# Music_Player_Module.net
KiCad netlist of a schematic drawn in EasyEDA
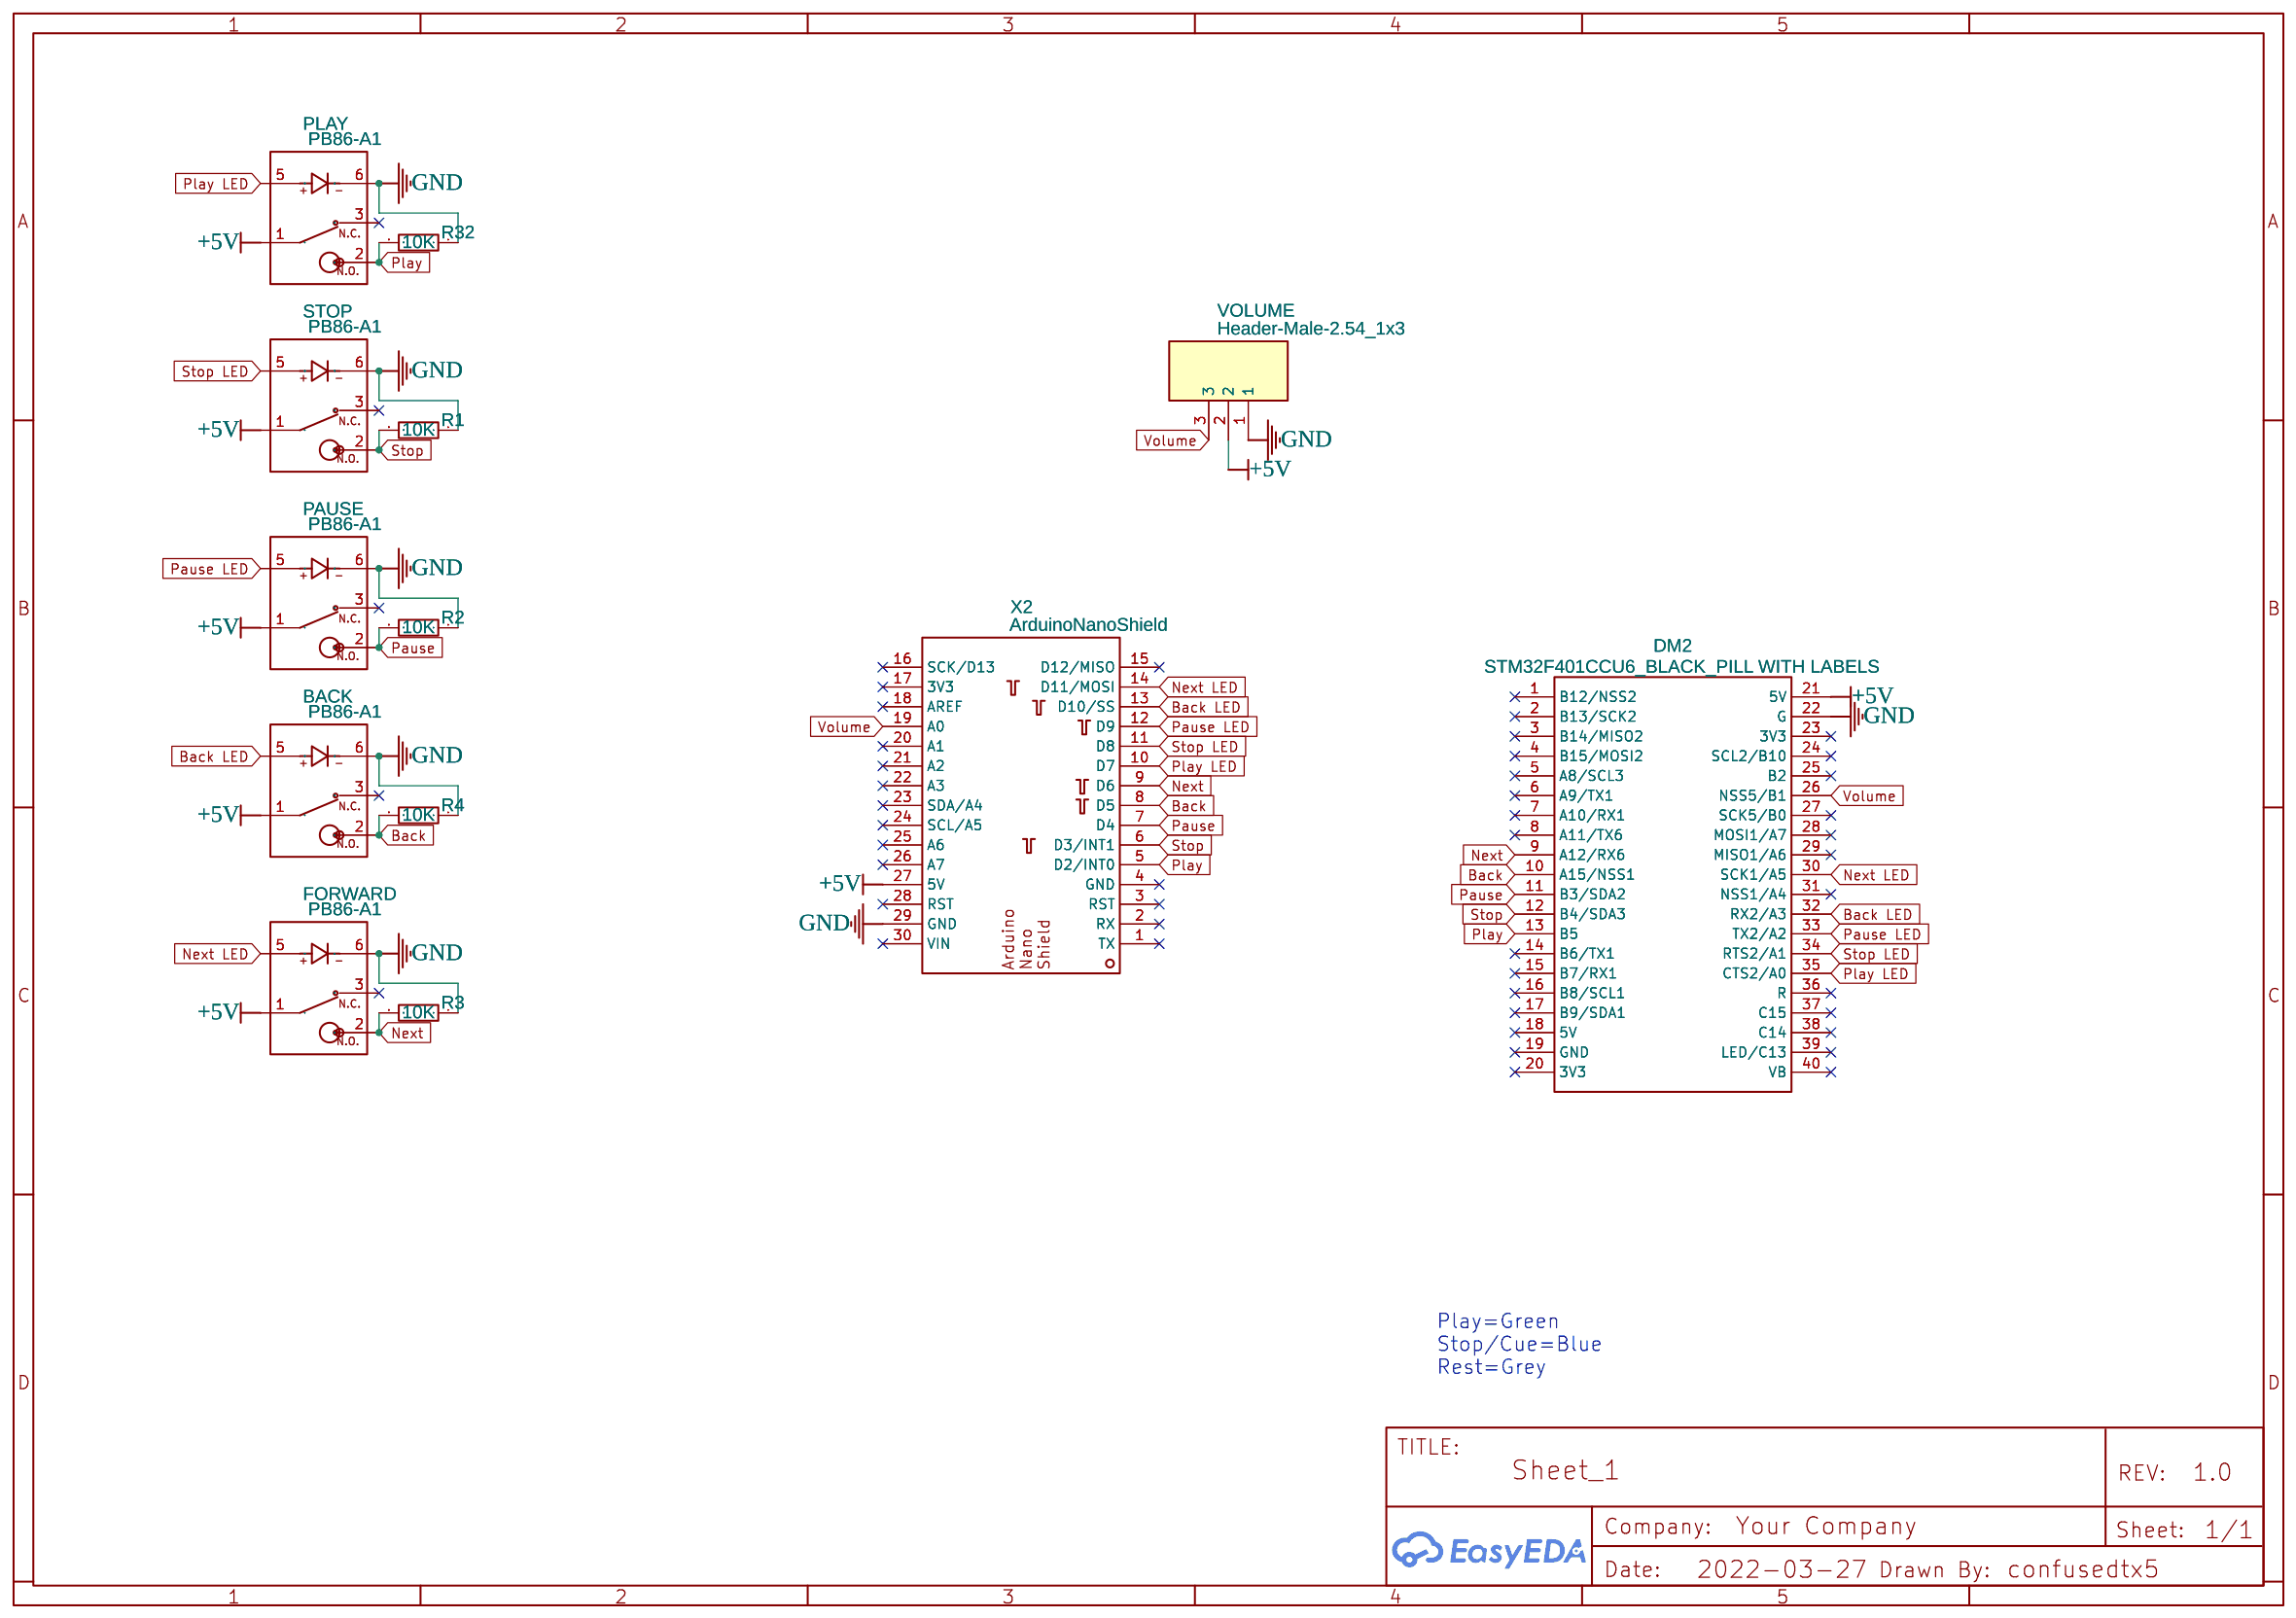
[diagram p0: schematic sheet]

(export (version "E")
  (design (tool "Eeschema 10.0.6"))
  (components
    (comp (ref "BACK") (value "PB86-A1") (libsource (lib "") (part "PB86-A1_3")))
    (comp (ref "DM2")
      (value "STM32F401CCU6_BLACK_PILL WITH LABELS")
      (libsource (lib "") (part "STM32F401CCU6_BLACK_PILL WITH LABELS"))
    )
    (comp (ref "FORWARD") (value "PB86-A1") (libsource (lib "") (part "PB86-A1")))
    (comp (ref "PAUSE") (value "PB86-A1") (libsource (lib "") (part "PB86-A1_4")))
    (comp (ref "PLAY") (value "PB86-A1") (libsource (lib "") (part "PB86-A1_1")))
    (comp (ref "R1")
      (value "10K")
      (fields
        (field (name "BOM_Manufacturer Part") "ESR03EZPJ103")
        (field (name "BOM_Supplier Part") "C253330")
      )
      (libsource (lib "") (part "ESR03EZPJ103"))
    )
    (comp (ref "R2")
      (value "10K")
      (fields
        (field (name "BOM_Manufacturer Part") "ESR03EZPJ103")
        (field (name "BOM_Supplier Part") "C253330")
      )
      (libsource (lib "") (part "ESR03EZPJ103"))
    )
    (comp (ref "R3")
      (value "10K")
      (fields
        (field (name "BOM_Manufacturer Part") "ESR03EZPJ103")
        (field (name "BOM_Supplier Part") "C253330")
      )
      (libsource (lib "") (part "ESR03EZPJ103"))
    )
    (comp (ref "R4")
      (value "10K")
      (fields
        (field (name "BOM_Manufacturer Part") "ESR03EZPJ103")
        (field (name "BOM_Supplier Part") "C253330")
      )
      (libsource (lib "") (part "ESR03EZPJ103"))
    )
    (comp (ref "R32")
      (value "10K")
      (fields
        (field (name "BOM_Manufacturer Part") "ESR03EZPJ103")
        (field (name "BOM_Supplier Part") "C253330")
      )
      (libsource (lib "") (part "ESR03EZPJ103"))
    )
    (comp (ref "STOP") (value "PB86-A1") (libsource (lib "") (part "PB86-A1_2")))
    (comp (ref "VOLUME")
      (value "Header-Male-2.54_1x3")
      (fields (field (name "BOM_Manufacturer Part") "Header-Male-2.54_1x10"))
      (libsource (lib "") (part "Header-Male-2.54_1x3"))
    )
    (comp (ref "X2") (value "ArduinoNanoShield") (libsource (lib "") (part "ArduinoNanoShield")))
  )
  (nets
    (net (code "1") (name "+5V") (class "Default")
      (node (ref "BACK") (pin "1") (pinfunction "1_1") (pintype "unspecified"))
      (node (ref "DM2") (pin "21") (pinfunction "5V_21") (pintype "unspecified"))
      (node (ref "FORWARD") (pin "1") (pinfunction "1_1") (pintype "unspecified"))
      (node (ref "PAUSE") (pin "1") (pinfunction "1_1") (pintype "unspecified"))
      (node (ref "PLAY") (pin "1") (pinfunction "1_1") (pintype "unspecified"))
      (node (ref "STOP") (pin "1") (pinfunction "1_1") (pintype "unspecified"))
      (node (ref "VOLUME") (pin "2") (pinfunction "2_2") (pintype "unspecified"))
      (node (ref "X2") (pin "27") (pinfunction "5V_27") (pintype "unspecified"))
    )
    (net (code "2") (name "Back") (class "Default")
      (node (ref "BACK") (pin "2") (pinfunction "2_2") (pintype "unspecified"))
      (node (ref "DM2") (pin "10") (pinfunction "A15/NSS1_10") (pintype "unspecified"))
      (node (ref "R4") (pin "2") (pinfunction "2_2") (pintype "unspecified"))
      (node (ref "X2") (pin "8") (pinfunction "D5_8") (pintype "unspecified"))
    )
    (net (code "3") (name "Back LED") (class "Default")
      (node (ref "BACK") (pin "5") (pinfunction "5_5") (pintype "unspecified"))
      (node (ref "DM2") (pin "32") (pinfunction "RX2/A3_32") (pintype "unspecified"))
      (node (ref "X2") (pin "13") (pinfunction "D10/SS_13") (pintype "unspecified"))
    )
    (net (code "4") (name "GND") (class "Default")
      (node (ref "BACK") (pin "6") (pinfunction "6_6") (pintype "unspecified"))
      (node (ref "DM2") (pin "22") (pinfunction "G_22") (pintype "unspecified"))
      (node (ref "FORWARD") (pin "6") (pinfunction "6_6") (pintype "unspecified"))
      (node (ref "PAUSE") (pin "6") (pinfunction "6_6") (pintype "unspecified"))
      (node (ref "PLAY") (pin "6") (pinfunction "6_6") (pintype "unspecified"))
      (node (ref "R1") (pin "1") (pinfunction "1_1") (pintype "unspecified"))
      (node (ref "R2") (pin "1") (pinfunction "1_1") (pintype "unspecified"))
      (node (ref "R3") (pin "1") (pinfunction "1_1") (pintype "unspecified"))
      (node (ref "R32") (pin "1") (pinfunction "1_1") (pintype "unspecified"))
      (node (ref "R4") (pin "1") (pinfunction "1_1") (pintype "unspecified"))
      (node (ref "STOP") (pin "6") (pinfunction "6_6") (pintype "unspecified"))
      (node (ref "VOLUME") (pin "1") (pinfunction "1_1") (pintype "unspecified"))
      (node (ref "X2") (pin "29") (pinfunction "GND_29") (pintype "unspecified"))
    )
    (net (code "5") (name "Next") (class "Default")
      (node (ref "DM2") (pin "9") (pinfunction "A12/RX6_9") (pintype "unspecified"))
      (node (ref "FORWARD") (pin "2") (pinfunction "2_2") (pintype "unspecified"))
      (node (ref "R3") (pin "2") (pinfunction "2_2") (pintype "unspecified"))
      (node (ref "X2") (pin "9") (pinfunction "D6_9") (pintype "unspecified"))
    )
    (net (code "6") (name "Next LED") (class "Default")
      (node (ref "DM2") (pin "30") (pinfunction "SCK1/A5_30") (pintype "unspecified"))
      (node (ref "FORWARD") (pin "5") (pinfunction "5_5") (pintype "unspecified"))
      (node (ref "X2") (pin "14") (pinfunction "D11/MOSI_14") (pintype "unspecified"))
    )
    (net (code "7") (name "Pause") (class "Default")
      (node (ref "DM2") (pin "11") (pinfunction "B3/SDA2_11") (pintype "unspecified"))
      (node (ref "PAUSE") (pin "2") (pinfunction "2_2") (pintype "unspecified"))
      (node (ref "R2") (pin "2") (pinfunction "2_2") (pintype "unspecified"))
      (node (ref "X2") (pin "7") (pinfunction "D4_7") (pintype "unspecified"))
    )
    (net (code "8") (name "Pause LED") (class "Default")
      (node (ref "DM2") (pin "33") (pinfunction "TX2/A2_33") (pintype "unspecified"))
      (node (ref "PAUSE") (pin "5") (pinfunction "5_5") (pintype "unspecified"))
      (node (ref "X2") (pin "12") (pinfunction "D9_12") (pintype "unspecified"))
    )
    (net (code "9") (name "Play") (class "Default")
      (node (ref "DM2") (pin "13") (pinfunction "B5_13") (pintype "unspecified"))
      (node (ref "PLAY") (pin "2") (pinfunction "2_2") (pintype "unspecified"))
      (node (ref "R32") (pin "2") (pinfunction "2_2") (pintype "unspecified"))
      (node (ref "X2") (pin "5") (pinfunction "D2/INT0_5") (pintype "unspecified"))
    )
    (net (code "10") (name "Play LED") (class "Default")
      (node (ref "DM2") (pin "35") (pinfunction "CTS2/A0_35") (pintype "unspecified"))
      (node (ref "PLAY") (pin "5") (pinfunction "5_5") (pintype "unspecified"))
      (node (ref "X2") (pin "10") (pinfunction "D7_10") (pintype "unspecified"))
    )
    (net (code "11") (name "Stop") (class "Default")
      (node (ref "DM2") (pin "12") (pinfunction "B4/SDA3_12") (pintype "unspecified"))
      (node (ref "R1") (pin "2") (pinfunction "2_2") (pintype "unspecified"))
      (node (ref "STOP") (pin "2") (pinfunction "2_2") (pintype "unspecified"))
      (node (ref "X2") (pin "6") (pinfunction "D3/INT1_6") (pintype "unspecified"))
    )
    (net (code "12") (name "Stop LED") (class "Default")
      (node (ref "DM2") (pin "34") (pinfunction "RTS2/A1_34") (pintype "unspecified"))
      (node (ref "STOP") (pin "5") (pinfunction "5_5") (pintype "unspecified"))
      (node (ref "X2") (pin "11") (pinfunction "D8_11") (pintype "unspecified"))
    )
    (net (code "13") (name "Volume") (class "Default")
      (node (ref "DM2") (pin "26") (pinfunction "NSS5/B1_26") (pintype "unspecified"))
      (node (ref "VOLUME") (pin "3") (pinfunction "3_3") (pintype "unspecified"))
      (node (ref "X2") (pin "19") (pinfunction "A0_19") (pintype "unspecified"))
    )
    (net (code "14") (name "unconnected-(BACK-Pad3)") (class "Default")
      (node (ref "BACK") (pin "3") (pinfunction "3_3") (pintype "unspecified+no_connect"))
    )
    (net (code "15") (name "unconnected-(DM2-3V3-Pad20)") (class "Default")
      (node (ref "DM2") (pin "20") (pinfunction "3V3_20") (pintype "unspecified+no_connect"))
    )
    (net (code "16") (name "unconnected-(DM2-3V3-Pad23)") (class "Default")
      (node (ref "DM2") (pin "23") (pinfunction "3V3_23") (pintype "unspecified+no_connect"))
    )
    (net (code "17") (name "unconnected-(DM2-5V-Pad18)") (class "Default")
      (node (ref "DM2") (pin "18") (pinfunction "5V_18") (pintype "unspecified+no_connect"))
    )
    (net (code "18") (name "unconnected-(DM2-A8{slash}SCL3-Pad5)") (class "Default")
      (node (ref "DM2") (pin "5") (pinfunction "A8/SCL3_5") (pintype "unspecified+no_connect"))
    )
    (net (code "19") (name "unconnected-(DM2-A9{slash}TX1-Pad6)") (class "Default")
      (node (ref "DM2") (pin "6") (pinfunction "A9/TX1_6") (pintype "unspecified+no_connect"))
    )
    (net (code "20") (name "unconnected-(DM2-A10{slash}RX1-Pad7)") (class "Default")
      (node (ref "DM2") (pin "7") (pinfunction "A10/RX1_7") (pintype "unspecified+no_connect"))
    )
    (net (code "21") (name "unconnected-(DM2-A11{slash}TX6-Pad8)") (class "Default")
      (node (ref "DM2") (pin "8") (pinfunction "A11/TX6_8") (pintype "unspecified+no_connect"))
    )
    (net (code "22") (name "unconnected-(DM2-B2-Pad25)") (class "Default")
      (node (ref "DM2") (pin "25") (pinfunction "B2_25") (pintype "unspecified+no_connect"))
    )
    (net (code "23") (name "unconnected-(DM2-B6{slash}TX1-Pad14)") (class "Default")
      (node (ref "DM2") (pin "14") (pinfunction "B6/TX1_14") (pintype "unspecified+no_connect"))
    )
    (net (code "24") (name "unconnected-(DM2-B7{slash}RX1-Pad15)") (class "Default")
      (node (ref "DM2") (pin "15") (pinfunction "B7/RX1_15") (pintype "unspecified+no_connect"))
    )
    (net (code "25") (name "unconnected-(DM2-B8{slash}SCL1-Pad16)") (class "Default")
      (node (ref "DM2") (pin "16") (pinfunction "B8/SCL1_16") (pintype "unspecified+no_connect"))
    )
    (net (code "26") (name "unconnected-(DM2-B9{slash}SDA1-Pad17)") (class "Default")
      (node (ref "DM2") (pin "17") (pinfunction "B9/SDA1_17") (pintype "unspecified+no_connect"))
    )
    (net (code "27") (name "unconnected-(DM2-B12{slash}NSS2-Pad1)") (class "Default")
      (node (ref "DM2") (pin "1") (pinfunction "B12/NSS2_1") (pintype "unspecified+no_connect"))
    )
    (net (code "28") (name "unconnected-(DM2-B13{slash}SCK2-Pad2)") (class "Default")
      (node (ref "DM2") (pin "2") (pinfunction "B13/SCK2_2") (pintype "unspecified+no_connect"))
    )
    (net (code "29") (name "unconnected-(DM2-B14{slash}MISO2-Pad3)") (class "Default")
      (node (ref "DM2") (pin "3") (pinfunction "B14/MISO2_3") (pintype "unspecified+no_connect"))
    )
    (net (code "30") (name "unconnected-(DM2-B15{slash}MOSI2-Pad4)") (class "Default")
      (node (ref "DM2") (pin "4") (pinfunction "B15/MOSI2_4") (pintype "unspecified+no_connect"))
    )
    (net (code "31") (name "unconnected-(DM2-C14-Pad38)") (class "Default")
      (node (ref "DM2") (pin "38") (pinfunction "C14_38") (pintype "unspecified+no_connect"))
    )
    (net (code "32") (name "unconnected-(DM2-C15-Pad37)") (class "Default")
      (node (ref "DM2") (pin "37") (pinfunction "C15_37") (pintype "unspecified+no_connect"))
    )
    (net (code "33") (name "unconnected-(DM2-GND-Pad19)") (class "Default")
      (node (ref "DM2") (pin "19") (pinfunction "GND_19") (pintype "unspecified+no_connect"))
    )
    (net (code "34") (name "unconnected-(DM2-LED{slash}C13-Pad39)") (class "Default")
      (node (ref "DM2") (pin "39") (pinfunction "LED/C13_39") (pintype "unspecified+no_connect"))
    )
    (net (code "35") (name "unconnected-(DM2-MISO1{slash}A6-Pad29)") (class "Default")
      (node (ref "DM2") (pin "29") (pinfunction "MISO1/A6_29") (pintype "unspecified+no_connect"))
    )
    (net (code "36") (name "unconnected-(DM2-MOSI1{slash}A7-Pad28)") (class "Default")
      (node (ref "DM2") (pin "28") (pinfunction "MOSI1/A7_28") (pintype "unspecified+no_connect"))
    )
    (net (code "37") (name "unconnected-(DM2-NSS1{slash}A4-Pad31)") (class "Default")
      (node (ref "DM2") (pin "31") (pinfunction "NSS1/A4_31") (pintype "unspecified+no_connect"))
    )
    (net (code "38") (name "unconnected-(DM2-R-Pad36)") (class "Default")
      (node (ref "DM2") (pin "36") (pinfunction "R_36") (pintype "unspecified+no_connect"))
    )
    (net (code "39") (name "unconnected-(DM2-SCK5{slash}B0-Pad27)") (class "Default")
      (node (ref "DM2") (pin "27") (pinfunction "SCK5/B0_27") (pintype "unspecified+no_connect"))
    )
    (net (code "40") (name "unconnected-(DM2-SCL2{slash}B10-Pad24)") (class "Default")
      (node (ref "DM2") (pin "24") (pinfunction "SCL2/B10_24") (pintype "unspecified+no_connect"))
    )
    (net (code "41") (name "unconnected-(DM2-VB-Pad40)") (class "Default")
      (node (ref "DM2") (pin "40") (pinfunction "VB_40") (pintype "unspecified+no_connect"))
    )
    (net (code "42") (name "unconnected-(FORWARD-Pad3)") (class "Default")
      (node (ref "FORWARD") (pin "3") (pinfunction "3_3") (pintype "unspecified+no_connect"))
    )
    (net (code "43") (name "unconnected-(PAUSE-Pad3)") (class "Default")
      (node (ref "PAUSE") (pin "3") (pinfunction "3_3") (pintype "unspecified+no_connect"))
    )
    (net (code "44") (name "unconnected-(PLAY-Pad3)") (class "Default")
      (node (ref "PLAY") (pin "3") (pinfunction "3_3") (pintype "unspecified+no_connect"))
    )
    (net (code "45") (name "unconnected-(STOP-Pad3)") (class "Default")
      (node (ref "STOP") (pin "3") (pinfunction "3_3") (pintype "unspecified+no_connect"))
    )
    (net (code "46") (name "unconnected-(X2-3V3-Pad17)") (class "Default")
      (node (ref "X2") (pin "17") (pinfunction "3V3_17") (pintype "unspecified+no_connect"))
    )
    (net (code "47") (name "unconnected-(X2-A1-Pad20)") (class "Default")
      (node (ref "X2") (pin "20") (pinfunction "A1_20") (pintype "unspecified+no_connect"))
    )
    (net (code "48") (name "unconnected-(X2-A2-Pad21)") (class "Default")
      (node (ref "X2") (pin "21") (pinfunction "A2_21") (pintype "unspecified+no_connect"))
    )
    (net (code "49") (name "unconnected-(X2-A3-Pad22)") (class "Default")
      (node (ref "X2") (pin "22") (pinfunction "A3_22") (pintype "unspecified+no_connect"))
    )
    (net (code "50") (name "unconnected-(X2-A6-Pad25)") (class "Default")
      (node (ref "X2") (pin "25") (pinfunction "A6_25") (pintype "unspecified+no_connect"))
    )
    (net (code "51") (name "unconnected-(X2-A7-Pad26)") (class "Default")
      (node (ref "X2") (pin "26") (pinfunction "A7_26") (pintype "unspecified+no_connect"))
    )
    (net (code "52") (name "unconnected-(X2-AREF-Pad18)") (class "Default")
      (node (ref "X2") (pin "18") (pinfunction "AREF_18") (pintype "unspecified+no_connect"))
    )
    (net (code "53") (name "unconnected-(X2-D12{slash}MISO-Pad15)") (class "Default")
      (node (ref "X2") (pin "15") (pinfunction "D12/MISO_15") (pintype "unspecified+no_connect"))
    )
    (net (code "54") (name "unconnected-(X2-GND-Pad4)") (class "Default")
      (node (ref "X2") (pin "4") (pinfunction "GND_4") (pintype "unspecified+no_connect"))
    )
    (net (code "55") (name "unconnected-(X2-RST-Pad3)") (class "Default")
      (node (ref "X2") (pin "3") (pinfunction "RST_3") (pintype "unspecified+no_connect"))
    )
    (net (code "56") (name "unconnected-(X2-RST-Pad28)") (class "Default")
      (node (ref "X2") (pin "28") (pinfunction "RST_28") (pintype "unspecified+no_connect"))
    )
    (net (code "57") (name "unconnected-(X2-RX-Pad2)") (class "Default")
      (node (ref "X2") (pin "2") (pinfunction "RX_2") (pintype "unspecified+no_connect"))
    )
    (net (code "58") (name "unconnected-(X2-SCK{slash}D13-Pad16)") (class "Default")
      (node (ref "X2") (pin "16") (pinfunction "SCK/D13_16") (pintype "unspecified+no_connect"))
    )
    (net (code "59") (name "unconnected-(X2-SCL{slash}A5-Pad24)") (class "Default")
      (node (ref "X2") (pin "24") (pinfunction "SCL/A5_24") (pintype "unspecified+no_connect"))
    )
    (net (code "60") (name "unconnected-(X2-SDA{slash}A4-Pad23)") (class "Default")
      (node (ref "X2") (pin "23") (pinfunction "SDA/A4_23") (pintype "unspecified+no_connect"))
    )
    (net (code "61") (name "unconnected-(X2-TX-Pad1)") (class "Default")
      (node (ref "X2") (pin "1") (pinfunction "TX_1") (pintype "unspecified+no_connect"))
    )
    (net (code "62") (name "unconnected-(X2-VIN-Pad30)") (class "Default")
      (node (ref "X2") (pin "30") (pinfunction "VIN_30") (pintype "unspecified+no_connect"))
    )
  )
)
